# lipovsky-control.net
KiCad netlist of a schematic drawn in EAGLE
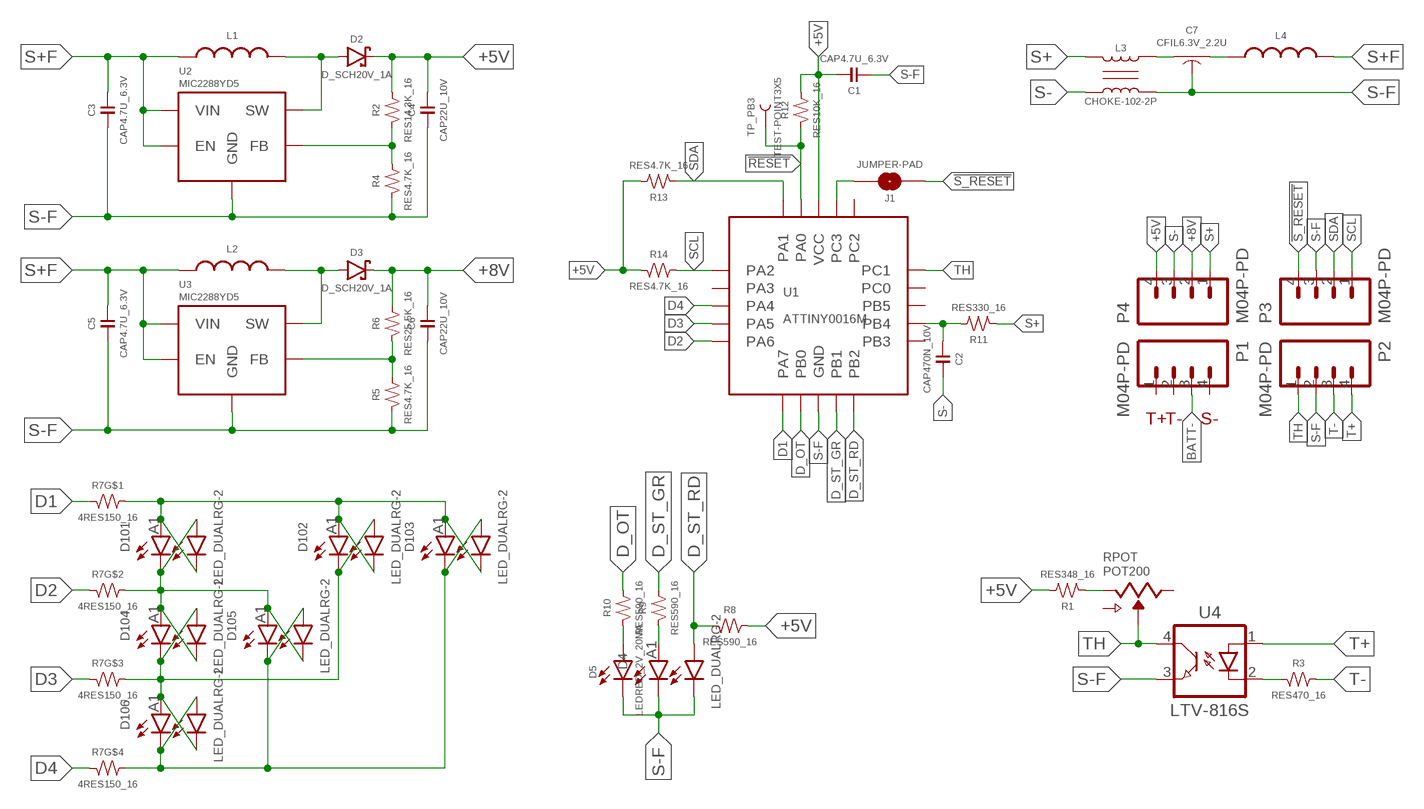
[diagram p0: schematic, sheet 1]

(export (version "E")
  (design (tool "Eeschema 10.0.6"))
  (components
    (comp (ref "C1")
      (value "CAP4.7U_6.3V")
      (footprint "eagle-import:0603")
      (fields
        (field (name "DIGIKEY_PART_#") "1276-2087-1-ND")
        (field (name "MANUFACTURER") "Samsung Electro-Mechanics America, Inc.")
        (field (name "MFG_PART_#") "CL10B475KQ8NQNC")
      )
      (libsource (lib "eagle-import") (part "CAP4.7U_6.3V"))
    )
    (comp (ref "C2")
      (value "CAP470N_10V")
      (footprint "eagle-import:0402")
      (fields
        (field (name "DIGIKEY_PART_#") "445-8009-1-ND")
        (field (name "MANUFACTURER") "TDK Corporation")
        (field (name "MFG_PART_#") "C1005X7S1A474K050BC")
      )
      (libsource (lib "eagle-import") (part "CAP470N_10V"))
    )
    (comp (ref "C3")
      (value "CAP4.7U_6.3V")
      (footprint "eagle-import:0603")
      (fields
        (field (name "DIGIKEY_PART_#") "1276-2087-1-ND")
        (field (name "MANUFACTURER") "Samsung Electro-Mechanics America, Inc.")
        (field (name "MFG_PART_#") "CL10B475KQ8NQNC")
      )
      (libsource (lib "eagle-import") (part "CAP4.7U_6.3V"))
    )
    (comp (ref "C4")
      (value "CAP22U_10V")
      (footprint "eagle-import:0603")
      (fields
        (field (name "DIGIKEY_PART_#") "1276-6504-1-ND")
        (field (name "MANUFACTURER") "Samsung Electro-Mechanics America, Inc.")
        (field (name "MFG_PART_#") "CL10A226MPCNUBE")
      )
      (libsource (lib "eagle-import") (part "CAP22U_10V"))
    )
    (comp (ref "C5")
      (value "CAP4.7U_6.3V")
      (footprint "eagle-import:0603")
      (fields
        (field (name "DIGIKEY_PART_#") "1276-2087-1-ND")
        (field (name "MANUFACTURER") "Samsung Electro-Mechanics America, Inc.")
        (field (name "MFG_PART_#") "CL10B475KQ8NQNC")
      )
      (libsource (lib "eagle-import") (part "CAP4.7U_6.3V"))
    )
    (comp (ref "C6")
      (value "CAP22U_10V")
      (footprint "eagle-import:0603")
      (fields
        (field (name "DIGIKEY_PART_#") "1276-6504-1-ND")
        (field (name "MANUFACTURER") "Samsung Electro-Mechanics America, Inc.")
        (field (name "MFG_PART_#") "CL10A226MPCNUBE")
      )
      (libsource (lib "eagle-import") (part "CAP22U_10V"))
    )
    (comp (ref "C7")
      (value "CFIL6.3V_2.2U")
      (footprint "eagle-import:CFIL-0603")
      (fields
        (field (name "MANUFACTURER") "Murata Electronics")
        (field (name "MFG_PART_#") "NFM18PC225B0J3D")
        (field (name "MOUSER_PART_#") "81-NFM18PC225B0J3D")
      )
      (libsource (lib "eagle-import") (part "CFIL6.3V_2.2U"))
    )
    (comp (ref "D2")
      (value "D_SCH20V_1A")
      (footprint "eagle-import:SOD523+")
      (fields
        (field (name "MANUFACTURER") "Nexperia")
        (field (name "MFG_PART_#") "PMEG2010AEB,115")
        (field (name "MOUSER_PART_#") "771-PMEG2010AEBT/R")
      )
      (libsource (lib "eagle-import") (part "D_SCH20V_1A"))
    )
    (comp (ref "D3")
      (value "D_SCH20V_1A")
      (footprint "eagle-import:SOD523+")
      (fields
        (field (name "MANUFACTURER") "Nexperia")
        (field (name "MFG_PART_#") "PMEG2010AEB,115")
        (field (name "MOUSER_PART_#") "771-PMEG2010AEBT/R")
      )
      (libsource (lib "eagle-import") (part "D_SCH20V_1A"))
    )
    (comp (ref "D4")
      (value "LED_DUALRG-2")
      (footprint "eagle-import:1206+DUAL")
      (fields
        (field (name "DIGIKEY_PART_#") "160-2026-1-ND")
        (field (name "MANUFACTURER") "Lite-On Inc.")
        (field (name "MFG_PART_#") "LTST-C235KGKRKT")
      )
      (libsource (lib "eagle-import") (part "LED_DUALRG-2"))
    )
    (comp (ref "D5")
      (value "LEDRED_2V_20MA")
      (footprint "eagle-import:1206+")
      (fields
        (field (name "DIGIKEY_PART_#") "160-1457-1-ND")
        (field (name "MANUFACTURER") "Lite-On Inc.")
        (field (name "MFG_PART_#") "LTST-C230KRKT")
      )
      (libsource (lib "eagle-import") (part "LEDRED_2V_20MA"))
    )
    (comp (ref "D101")
      (value "LED_DUALRG-2")
      (footprint "eagle-import:1206+DUAL")
      (fields
        (field (name "DIGIKEY_PART_#") "160-2026-1-ND")
        (field (name "MANUFACTURER") "Lite-On Inc.")
        (field (name "MFG_PART_#") "LTST-C235KGKRKT")
      )
      (libsource (lib "eagle-import") (part "LED_DUALRG-2"))
    )
    (comp (ref "D102")
      (value "LED_DUALRG-2")
      (footprint "eagle-import:1206+DUAL")
      (fields
        (field (name "DIGIKEY_PART_#") "160-2026-1-ND")
        (field (name "MANUFACTURER") "Lite-On Inc.")
        (field (name "MFG_PART_#") "LTST-C235KGKRKT")
      )
      (libsource (lib "eagle-import") (part "LED_DUALRG-2"))
    )
    (comp (ref "D103")
      (value "LED_DUALRG-2")
      (footprint "eagle-import:1206+DUAL")
      (fields
        (field (name "DIGIKEY_PART_#") "160-2026-1-ND")
        (field (name "MANUFACTURER") "Lite-On Inc.")
        (field (name "MFG_PART_#") "LTST-C235KGKRKT")
      )
      (libsource (lib "eagle-import") (part "LED_DUALRG-2"))
    )
    (comp (ref "D104")
      (value "LED_DUALRG-2")
      (footprint "eagle-import:1206+DUAL")
      (fields
        (field (name "DIGIKEY_PART_#") "160-2026-1-ND")
        (field (name "MANUFACTURER") "Lite-On Inc.")
        (field (name "MFG_PART_#") "LTST-C235KGKRKT")
      )
      (libsource (lib "eagle-import") (part "LED_DUALRG-2"))
    )
    (comp (ref "D105")
      (value "LED_DUALRG-2")
      (footprint "eagle-import:1206+DUAL")
      (fields
        (field (name "DIGIKEY_PART_#") "160-2026-1-ND")
        (field (name "MANUFACTURER") "Lite-On Inc.")
        (field (name "MFG_PART_#") "LTST-C235KGKRKT")
      )
      (libsource (lib "eagle-import") (part "LED_DUALRG-2"))
    )
    (comp (ref "D106")
      (value "LED_DUALRG-2")
      (footprint "eagle-import:1206+DUAL")
      (fields
        (field (name "DIGIKEY_PART_#") "160-2026-1-ND")
        (field (name "MANUFACTURER") "Lite-On Inc.")
        (field (name "MFG_PART_#") "LTST-C235KGKRKT")
      )
      (libsource (lib "eagle-import") (part "LED_DUALRG-2"))
    )
    (comp (ref "J1")
      (value "JUMPER-PAD")
      (footprint "eagle-import:JUMPER-PAD-ROUND")
      (libsource (lib "eagle-import") (part "JUMPER-PAD"))
    )
    (comp (ref "L1")
      (value "I4.7U_0.12A")
      (footprint "eagle-import:0603")
      (fields
        (field (name "DIGIKEY_PART_#") "445-6390-1-ND")
        (field (name "MANUFACTURER") "TDK Corporation")
        (field (name "MFG_PART_#") "MLZ1608M4R7WT000")
      )
      (libsource (lib "eagle-import") (part "I4.7U_0.12A"))
    )
    (comp (ref "L2")
      (value "I10U_0.09A")
      (footprint "eagle-import:0603")
      (fields
        (field (name "DIGIKEY_PART_#") "445-6389-1-ND")
        (field (name "MANUFACTURER") "TDK Corporation")
        (field (name "MFG_PART_#") "MLZ1608M100WT000")
      )
      (libsource (lib "eagle-import") (part "I10U_0.09A"))
    )
    (comp (ref "L3")
      (value "CHOKE-102-2P")
      (footprint "eagle-import:APC3225")
      (fields
        (field (name "DIGIKEY_PART_#") "445-174210-1-ND")
        (field (name "MANUFACTURER") "TDK Corporation")
        (field (name "MFG_PART_#") "ACP3225-102-2P-TL000")
      )
      (libsource (lib "eagle-import") (part "CHOKE-102-2P"))
    )
    (comp (ref "L4")
      (value "I3.3UH_1A")
      (footprint "eagle-import:0603")
      (fields
        (field (name "DIGIKEY_PART_#") "490-15635-1-ND")
        (field (name "MANUFACTURER") "Murata Electronics North America")
        (field (name "MFG_PART_#") "LQM18PN3R3MGHD")
      )
      (libsource (lib "eagle-import") (part "I3.3UH_1A"))
    )
    (comp (ref "P1")
      (value "M04P-PD")
      (footprint "eagle-import:1X04_929P")
      (fields
        (field (name "DIGIKEY_PART_#") "890-70-004-10-001101-ND")
        (field (name "MANUFACTURER") "Preci-dip")
        (field (name "MFG_PART_#") "890-70-004-10-001101")
      )
      (libsource (lib "eagle-import") (part "M04P-PD"))
    )
    (comp (ref "P2")
      (value "M04P-PD")
      (footprint "eagle-import:1X04_929P")
      (fields
        (field (name "DIGIKEY_PART_#") "890-70-004-10-001101-ND")
        (field (name "MANUFACTURER") "Preci-dip")
        (field (name "MFG_PART_#") "890-70-004-10-001101")
      )
      (libsource (lib "eagle-import") (part "M04P-PD"))
    )
    (comp (ref "P3")
      (value "M04P-PD")
      (footprint "eagle-import:1X04_929P")
      (fields
        (field (name "DIGIKEY_PART_#") "890-70-004-10-001101-ND")
        (field (name "MANUFACTURER") "Preci-dip")
        (field (name "MFG_PART_#") "890-70-004-10-001101")
      )
      (libsource (lib "eagle-import") (part "M04P-PD"))
    )
    (comp (ref "P4")
      (value "M04P-PD")
      (footprint "eagle-import:1X04_929P")
      (fields
        (field (name "DIGIKEY_PART_#") "890-70-004-10-001101-ND")
        (field (name "MANUFACTURER") "Preci-dip")
        (field (name "MFG_PART_#") "890-70-004-10-001101")
      )
      (libsource (lib "eagle-import") (part "M04P-PD"))
    )
    (comp (ref "R1")
      (value "RES348_16")
      (footprint "eagle-import:0402")
      (fields
        (field (name "DIGIKEY_PART_#") "541-348LCT-ND")
        (field (name "MANUFACTURER") "Vishay Dale")
        (field (name "MFG_PART_#") "CRCW0402348RFKED")
      )
      (libsource (lib "eagle-import") (part "RES348_16"))
    )
    (comp (ref "R2")
      (value "RES14.3K_16")
      (footprint "eagle-import:0402")
      (fields
        (field (name "DIGIKEY_PART_#") "541-14.3KLCT-ND")
        (field (name "MANUFACTURER") "Vishay Dale")
        (field (name "MFG_PART_#") "CRCW040214K3FKED")
      )
      (libsource (lib "eagle-import") (part "RES14.3K_16"))
    )
    (comp (ref "R3")
      (value "RES470_16")
      (footprint "eagle-import:0402")
      (fields
        (field (name "DIGIKEY_PART_#") "541-470LCT-ND")
        (field (name "MANUFACTURER") "Vishay Dale")
        (field (name "MFG_PART_#") "CRCW0402470RFKED")
      )
      (libsource (lib "eagle-import") (part "RES470_16"))
    )
    (comp (ref "R4")
      (value "RES4.7K_16")
      (footprint "eagle-import:0402")
      (fields
        (field (name "DIGIKEY_PART_#") "541-4.70KLCT-ND")
        (field (name "MANUFACTURER") "Vishay Dale")
        (field (name "MFG_PART_#") "CRCW04024K70FKED")
      )
      (libsource (lib "eagle-import") (part "RES4.7K_16"))
    )
    (comp (ref "R5")
      (value "RES4.7K_16")
      (footprint "eagle-import:0402")
      (fields
        (field (name "DIGIKEY_PART_#") "541-4.70KLCT-ND")
        (field (name "MANUFACTURER") "Vishay Dale")
        (field (name "MFG_PART_#") "CRCW04024K70FKED")
      )
      (libsource (lib "eagle-import") (part "RES4.7K_16"))
    )
    (comp (ref "R6")
      (value "RES25.5K_16")
      (footprint "eagle-import:0402")
      (fields
        (field (name "DIGIKEY_PART_#") "541-25.5KLCT-ND")
        (field (name "MANUFACTURER") "Vishay Dale")
        (field (name "MFG_PART_#") "CRCW040225K5FKED")
      )
      (libsource (lib "eagle-import") (part "RES25.5K_16"))
    )
    (comp (ref "R7")
      (value "4RES150_16")
      (footprint "eagle-import:1206-QUAD-LS")
      (fields
        (field (name "DIGIKEY_PART_#") "Y4151CT-ND")
        (field (name "MANUFACTURER") "Panasonic Electronic Components")
        (field (name "MFG_PART_#") "EXB-V8V151JV")
      )
      (libsource (lib "eagle-import") (part "4RES150_16"))
    )
    (comp (ref "R8")
      (value "RES590_16")
      (footprint "eagle-import:0402")
      (fields
        (field (name "DIGIKEY_PART_#") "541-590LCT-ND")
        (field (name "MANUFACTURER") "Vishay Dale")
        (field (name "MFG_PART_#") "CRCW0402590RFKED")
      )
      (libsource (lib "eagle-import") (part "RES590_16"))
    )
    (comp (ref "R9")
      (value "RES590_16")
      (footprint "eagle-import:0402")
      (fields
        (field (name "DIGIKEY_PART_#") "541-590LCT-ND")
        (field (name "MANUFACTURER") "Vishay Dale")
        (field (name "MFG_PART_#") "CRCW0402590RFKED")
      )
      (libsource (lib "eagle-import") (part "RES590_16"))
    )
    (comp (ref "R10")
      (value "RES590_16")
      (footprint "eagle-import:0402")
      (fields
        (field (name "DIGIKEY_PART_#") "541-590LCT-ND")
        (field (name "MANUFACTURER") "Vishay Dale")
        (field (name "MFG_PART_#") "CRCW0402590RFKED")
      )
      (libsource (lib "eagle-import") (part "RES590_16"))
    )
    (comp (ref "R11")
      (value "RES330_16")
      (footprint "eagle-import:0402")
      (fields
        (field (name "DIGIKEY_PART_#") "541-330LCT-ND")
        (field (name "MANUFACTURER") "Vishay Dale")
        (field (name "MFG_PART_#") "CRCW0402330RFKED")
      )
      (libsource (lib "eagle-import") (part "RES330_16"))
    )
    (comp (ref "R12")
      (value "RES10K_16")
      (footprint "eagle-import:0402")
      (fields
        (field (name "DIGIKEY_PART_#") "541-10.0KLCT-ND")
        (field (name "MANUFACTURER") "Vishay Dale")
        (field (name "MFG_PART_#") "CRCW040210K0FKED")
      )
      (libsource (lib "eagle-import") (part "RES10K_16"))
    )
    (comp (ref "R13")
      (value "RES4.7K_16")
      (footprint "eagle-import:0402")
      (fields
        (field (name "DIGIKEY_PART_#") "541-4.70KLCT-ND")
        (field (name "MANUFACTURER") "Vishay Dale")
        (field (name "MFG_PART_#") "CRCW04024K70FKED")
      )
      (libsource (lib "eagle-import") (part "RES4.7K_16"))
    )
    (comp (ref "R14")
      (value "RES4.7K_16")
      (footprint "eagle-import:0402")
      (fields
        (field (name "DIGIKEY_PART_#") "541-4.70KLCT-ND")
        (field (name "MANUFACTURER") "Vishay Dale")
        (field (name "MFG_PART_#") "CRCW04024K70FKED")
      )
      (libsource (lib "eagle-import") (part "RES4.7K_16"))
    )
    (comp (ref "RPOT")
      (value "POT200")
      (footprint "eagle-import:TC33")
      (fields
        (field (name "DIGIKEY_PART_#") "TC33X-2-201ECT-ND")
        (field (name "MANUFACTURER") "Bourns Inc.")
        (field (name "MFG_PART_#") "TC33X-2-201E")
      )
      (libsource (lib "eagle-import") (part "POT200"))
    )
    (comp (ref "TP_PB3")
      (value "TEST-POINT3X5")
      (footprint "eagle-import:PAD.03X.05")
      (libsource (lib "eagle-import") (part "TEST-POINT3X5"))
    )
    (comp (ref "U1")
      (value "ATTINY0016M")
      (footprint "eagle-import:20-VQFN-2")
      (fields
        (field (name "DIGIKEY_PART_#") "ATTINY1616-MFRCT-ND")
        (field (name "MANUFACTURER") "Microchip Technology")
        (field (name "MFG_PART_#") "ATTINY1616-MFR")
      )
      (libsource (lib "eagle-import") (part "ATTINY0016M"))
    )
    (comp (ref "U2")
      (value "MIC2288YD5")
      (footprint "eagle-import:SOT-23-5")
      (fields
        (field (name "DIGIKEY_PART_#") "576-1729-1-ND")
        (field (name "MANUFACTURER") "Microchip Technology")
        (field (name "MFG_PART_#") "MIC2288YD5-TR")
      )
      (libsource (lib "eagle-import") (part "MIC2288YD5"))
    )
    (comp (ref "U3")
      (value "MIC2288YD5")
      (footprint "eagle-import:SOT-23-5")
      (fields
        (field (name "DIGIKEY_PART_#") "576-1729-1-ND")
        (field (name "MANUFACTURER") "Microchip Technology")
        (field (name "MFG_PART_#") "MIC2288YD5-TR")
      )
      (libsource (lib "eagle-import") (part "MIC2288YD5"))
    )
    (comp (ref "U4")
      (value "LTV-816S")
      (footprint "eagle-import:4-OPTO-1")
      (fields (field (name "DIGIKEY_PART_#") "160-1361-5-ND") (field (name "MANUFACTURER") "Lite-On Inc."))
      (libsource (lib "eagle-import") (part "LTV-816S"))
    )
  )
  (nets
    (net (code "1") (name "+5V") (class "Default")
      (node (ref "C1") (pin "2") (pinfunction "2_2") (pintype "passive"))
      (node (ref "C4") (pin "2") (pinfunction "2_2") (pintype "passive"))
      (node (ref "D2") (pin "C") (pinfunction "C_C") (pintype "passive"))
      (node (ref "P4") (pin "4") (pinfunction "4_4") (pintype "passive"))
      (node (ref "R1") (pin "2") (pinfunction "2_2") (pintype "passive"))
      (node (ref "R12") (pin "2") (pinfunction "2_2") (pintype "passive"))
      (node (ref "R13") (pin "2") (pinfunction "2_2") (pintype "passive"))
      (node (ref "R14") (pin "1") (pinfunction "1_1") (pintype "passive"))
      (node (ref "R2") (pin "2") (pinfunction "2_2") (pintype "passive"))
      (node (ref "R8") (pin "2") (pinfunction "2_2") (pintype "passive"))
      (node (ref "U1") (pin "4") (pinfunction "VCC_4") (pintype "passive"))
    )
    (net (code "2") (name "+8V") (class "Default")
      (node (ref "C6") (pin "2") (pinfunction "2_2") (pintype "passive"))
      (node (ref "D3") (pin "C") (pinfunction "C_C") (pintype "passive"))
      (node (ref "P4") (pin "2") (pinfunction "2_2") (pintype "passive"))
      (node (ref "R6") (pin "2") (pinfunction "2_2") (pintype "passive"))
    )
    (net (code "3") (name "/~{RESET}") (class "Default")
      (node (ref "R12") (pin "1") (pinfunction "1_1") (pintype "passive"))
      (node (ref "TP_PB3") (pin "P$1") (pinfunction "1_P$1") (pintype "bidirectional"))
      (node (ref "U1") (pin "19") (pinfunction "PA0_19") (pintype "passive"))
    )
    (net (code "4") (name "/~{S_RESET}") (class "Default")
      (node (ref "J1") (pin "1") (pinfunction "1_1") (pintype "passive"))
      (node (ref "P3") (pin "4") (pinfunction "4_4") (pintype "passive"))
    )
    (net (code "5") (name "BATT-") (class "Default")
      (node (ref "P1") (pin "3") (pinfunction "3_3") (pintype "passive"))
    )
    (net (code "6") (name "D1") (class "Default")
      (node (ref "R7") (pin "1") (pinfunction "1_1") (pintype "passive"))
      (node (ref "U1") (pin "8") (pinfunction "PA7_8") (pintype "passive"))
    )
    (net (code "7") (name "D2") (class "Default")
      (node (ref "R7") (pin "2") (pinfunction "1_2") (pintype "passive"))
      (node (ref "U1") (pin "7") (pinfunction "PA6_7") (pintype "passive"))
    )
    (net (code "8") (name "D3") (class "Default")
      (node (ref "R7") (pin "3") (pinfunction "1_3") (pintype "passive"))
      (node (ref "U1") (pin "6") (pinfunction "PA5_6") (pintype "passive"))
    )
    (net (code "9") (name "D4") (class "Default")
      (node (ref "R7") (pin "4") (pinfunction "1_4") (pintype "passive"))
      (node (ref "U1") (pin "5") (pinfunction "PA4_5") (pintype "passive"))
    )
    (net (code "10") (name "D_OT") (class "Default")
      (node (ref "R10") (pin "2") (pinfunction "2_2") (pintype "passive"))
      (node (ref "U1") (pin "14") (pinfunction "PB0_14") (pintype "passive"))
    )
    (net (code "11") (name "D_ST_GR") (class "Default")
      (node (ref "R9") (pin "2") (pinfunction "2_2") (pintype "passive"))
      (node (ref "U1") (pin "13") (pinfunction "PB1_13") (pintype "passive"))
    )
    (net (code "12") (name "D_ST_RD") (class "Default")
      (node (ref "D4") (pin "A2") (pinfunction "A2_A2") (pintype "passive"))
      (node (ref "R8") (pin "1") (pinfunction "1_1") (pintype "passive"))
      (node (ref "U1") (pin "12") (pinfunction "PB2_12") (pintype "passive"))
    )
    (net (code "13") (name "Net-(C7-Pad2)") (class "Default")
      (node (ref "C7") (pin "2") (pinfunction "2_2") (pintype "passive"))
      (node (ref "L4") (pin "1") (pinfunction "1_1") (pintype "passive"))
    )
    (net (code "14") (name "Net-(D4-PadA1)") (class "Default")
      (node (ref "D4") (pin "A1") (pinfunction "A1_A1") (pintype "passive"))
      (node (ref "R9") (pin "1") (pinfunction "1_1") (pintype "passive"))
    )
    (net (code "15") (name "Net-(D5-PadA)") (class "Default")
      (node (ref "D5") (pin "A") (pinfunction "A_A") (pintype "passive"))
      (node (ref "R10") (pin "1") (pinfunction "1_1") (pintype "passive"))
    )
    (net (code "16") (name "Net-(L3-4)") (class "Default")
      (node (ref "C7") (pin "1") (pinfunction "1_1") (pintype "passive"))
      (node (ref "L3") (pin "P$4") (pinfunction "4_P$4") (pintype "passive"))
    )
    (net (code "17") (name "Net-(R1-Pad1)") (class "Default")
      (node (ref "R1") (pin "1") (pinfunction "1_1") (pintype "passive"))
      (node (ref "RPOT") (pin "CCW") (pinfunction "CCW_CCW") (pintype "passive"))
    )
    (net (code "18") (name "Net-(R7A-2)") (class "Default")
      (node (ref "D101") (pin "A1") (pinfunction "A1_A1") (pintype "passive"))
      (node (ref "D101") (pin "C2") (pinfunction "C2_C2") (pintype "passive"))
      (node (ref "D102") (pin "A1") (pinfunction "A1_A1") (pintype "passive"))
      (node (ref "D102") (pin "C2") (pinfunction "C2_C2") (pintype "passive"))
      (node (ref "D103") (pin "A1") (pinfunction "A1_A1") (pintype "passive"))
      (node (ref "D103") (pin "C2") (pinfunction "C2_C2") (pintype "passive"))
      (node (ref "R7") (pin "8") (pinfunction "2_8") (pintype "passive"))
    )
    (net (code "19") (name "Net-(R7B-2)") (class "Default")
      (node (ref "D101") (pin "A2") (pinfunction "A2_A2") (pintype "passive"))
      (node (ref "D101") (pin "C1") (pinfunction "C1_C1") (pintype "passive"))
      (node (ref "D104") (pin "A1") (pinfunction "A1_A1") (pintype "passive"))
      (node (ref "D104") (pin "C2") (pinfunction "C2_C2") (pintype "passive"))
      (node (ref "D105") (pin "A1") (pinfunction "A1_A1") (pintype "passive"))
      (node (ref "D105") (pin "C2") (pinfunction "C2_C2") (pintype "passive"))
      (node (ref "R7") (pin "7") (pinfunction "2_7") (pintype "passive"))
    )
    (net (code "20") (name "Net-(R7C-2)") (class "Default")
      (node (ref "D102") (pin "A2") (pinfunction "A2_A2") (pintype "passive"))
      (node (ref "D102") (pin "C1") (pinfunction "C1_C1") (pintype "passive"))
      (node (ref "D104") (pin "A2") (pinfunction "A2_A2") (pintype "passive"))
      (node (ref "D104") (pin "C1") (pinfunction "C1_C1") (pintype "passive"))
      (node (ref "D106") (pin "A1") (pinfunction "A1_A1") (pintype "passive"))
      (node (ref "D106") (pin "C2") (pinfunction "C2_C2") (pintype "passive"))
      (node (ref "R7") (pin "6") (pinfunction "2_6") (pintype "passive"))
    )
    (net (code "21") (name "Net-(R7D-2)") (class "Default")
      (node (ref "D103") (pin "A2") (pinfunction "A2_A2") (pintype "passive"))
      (node (ref "D103") (pin "C1") (pinfunction "C1_C1") (pintype "passive"))
      (node (ref "D105") (pin "A2") (pinfunction "A2_A2") (pintype "passive"))
      (node (ref "D105") (pin "C1") (pinfunction "C1_C1") (pintype "passive"))
      (node (ref "D106") (pin "A2") (pinfunction "A2_A2") (pintype "passive"))
      (node (ref "D106") (pin "C1") (pinfunction "C1_C1") (pintype "passive"))
      (node (ref "R7") (pin "5") (pinfunction "2_5") (pintype "passive"))
    )
    (net (code "22") (name "Net-(U1-PB4)") (class "Default")
      (node (ref "C2") (pin "1") (pinfunction "1_1") (pintype "passive"))
      (node (ref "R11") (pin "2") (pinfunction "2_2") (pintype "passive"))
      (node (ref "U1") (pin "10") (pinfunction "PB4_10") (pintype "passive"))
    )
    (net (code "23") (name "Net-(U1-PC3)") (class "Default")
      (node (ref "J1") (pin "2") (pinfunction "2_2") (pintype "passive"))
      (node (ref "U1") (pin "18") (pinfunction "PC3_18") (pintype "passive"))
    )
    (net (code "24") (name "Net-(U2-FB)") (class "Default")
      (node (ref "R2") (pin "1") (pinfunction "1_1") (pintype "passive"))
      (node (ref "R4") (pin "2") (pinfunction "2_2") (pintype "passive"))
      (node (ref "U2") (pin "3") (pinfunction "FB_3") (pintype "passive"))
    )
    (net (code "25") (name "Net-(U2-SW)") (class "Default")
      (node (ref "D2") (pin "A") (pinfunction "A_A") (pintype "passive"))
      (node (ref "L1") (pin "2") (pinfunction "2_2") (pintype "passive"))
      (node (ref "U2") (pin "1") (pinfunction "SW_1") (pintype "passive"))
    )
    (net (code "26") (name "Net-(U3-FB)") (class "Default")
      (node (ref "R5") (pin "2") (pinfunction "2_2") (pintype "passive"))
      (node (ref "R6") (pin "1") (pinfunction "1_1") (pintype "passive"))
      (node (ref "U3") (pin "3") (pinfunction "FB_3") (pintype "passive"))
    )
    (net (code "27") (name "Net-(U3-SW)") (class "Default")
      (node (ref "D3") (pin "A") (pinfunction "A_A") (pintype "passive"))
      (node (ref "L2") (pin "2") (pinfunction "2_2") (pintype "passive"))
      (node (ref "U3") (pin "1") (pinfunction "SW_1") (pintype "passive"))
    )
    (net (code "28") (name "Net-(U4-K)") (class "Default")
      (node (ref "R3") (pin "1") (pinfunction "1_1") (pintype "passive"))
      (node (ref "U4") (pin "2") (pinfunction "K_2") (pintype "passive"))
    )
    (net (code "29") (name "S+") (class "Default")
      (node (ref "L3") (pin "P$1") (pinfunction "1_P$1") (pintype "passive"))
      (node (ref "P4") (pin "1") (pinfunction "1_1") (pintype "passive"))
      (node (ref "R11") (pin "1") (pinfunction "1_1") (pintype "passive"))
    )
    (net (code "30") (name "S+F") (class "Default")
      (node (ref "C3") (pin "2") (pinfunction "2_2") (pintype "passive"))
      (node (ref "C5") (pin "2") (pinfunction "2_2") (pintype "passive"))
      (node (ref "L1") (pin "1") (pinfunction "1_1") (pintype "passive"))
      (node (ref "L2") (pin "1") (pinfunction "1_1") (pintype "passive"))
      (node (ref "L4") (pin "2") (pinfunction "2_2") (pintype "passive"))
      (node (ref "U2") (pin "4") (pinfunction "EN_4") (pintype "passive"))
      (node (ref "U2") (pin "5") (pinfunction "VIN_5") (pintype "passive"))
      (node (ref "U3") (pin "4") (pinfunction "EN_4") (pintype "passive"))
      (node (ref "U3") (pin "5") (pinfunction "VIN_5") (pintype "passive"))
    )
    (net (code "31") (name "S-") (class "Default")
      (node (ref "C2") (pin "2") (pinfunction "2_2") (pintype "passive"))
      (node (ref "L3") (pin "P$2") (pinfunction "2_P$2") (pintype "passive"))
      (node (ref "P4") (pin "3") (pinfunction "3_3") (pintype "passive"))
    )
    (net (code "32") (name "S-F") (class "Default")
      (node (ref "C1") (pin "1") (pinfunction "1_1") (pintype "passive"))
      (node (ref "C3") (pin "1") (pinfunction "1_1") (pintype "passive"))
      (node (ref "C4") (pin "1") (pinfunction "1_1") (pintype "passive"))
      (node (ref "C5") (pin "1") (pinfunction "1_1") (pintype "passive"))
      (node (ref "C6") (pin "1") (pinfunction "1_1") (pintype "passive"))
      (node (ref "C7") (pin "GND") (pinfunction "GND_GND") (pintype "passive"))
      (node (ref "D4") (pin "C1") (pinfunction "C1_C1") (pintype "passive"))
      (node (ref "D4") (pin "C2") (pinfunction "C2_C2") (pintype "passive"))
      (node (ref "D5") (pin "C") (pinfunction "C_C") (pintype "passive"))
      (node (ref "L3") (pin "P$3") (pinfunction "3_P$3") (pintype "passive"))
      (node (ref "P2") (pin "2") (pinfunction "2_2") (pintype "passive"))
      (node (ref "P3") (pin "3") (pinfunction "3_3") (pintype "passive"))
      (node (ref "R4") (pin "1") (pinfunction "1_1") (pintype "passive"))
      (node (ref "R5") (pin "1") (pinfunction "1_1") (pintype "passive"))
      (node (ref "U1") (pin "3") (pinfunction "GND_3") (pintype "passive"))
      (node (ref "U1") (pin "PAD") (pinfunction "GND_PAD") (pintype "passive"))
      (node (ref "U2") (pin "2") (pinfunction "GND_2") (pintype "passive"))
      (node (ref "U3") (pin "2") (pinfunction "GND_2") (pintype "passive"))
      (node (ref "U4") (pin "3") (pinfunction "E_3") (pintype "passive"))
    )
    (net (code "33") (name "SCL") (class "Default")
      (node (ref "P3") (pin "1") (pinfunction "1_1") (pintype "passive"))
      (node (ref "R14") (pin "2") (pinfunction "2_2") (pintype "passive"))
      (node (ref "U1") (pin "1") (pinfunction "PA2_1") (pintype "passive"))
    )
    (net (code "34") (name "SDA") (class "Default")
      (node (ref "P3") (pin "2") (pinfunction "2_2") (pintype "passive"))
      (node (ref "R13") (pin "1") (pinfunction "1_1") (pintype "passive"))
      (node (ref "U1") (pin "20") (pinfunction "PA1_20") (pintype "passive"))
    )
    (net (code "35") (name "T+") (class "Default")
      (node (ref "P2") (pin "4") (pinfunction "4_4") (pintype "passive"))
      (node (ref "U4") (pin "1") (pinfunction "A_1") (pintype "passive"))
    )
    (net (code "36") (name "T-") (class "Default")
      (node (ref "P2") (pin "3") (pinfunction "3_3") (pintype "passive"))
      (node (ref "R3") (pin "2") (pinfunction "2_2") (pintype "passive"))
    )
    (net (code "37") (name "TH") (class "Default")
      (node (ref "P2") (pin "1") (pinfunction "1_1") (pintype "passive"))
      (node (ref "RPOT") (pin "WIPER") (pinfunction "WIPER_WIPER") (pintype "passive"))
      (node (ref "U1") (pin "16") (pinfunction "PC1_16") (pintype "passive"))
      (node (ref "U4") (pin "4") (pinfunction "C_4") (pintype "passive"))
    )
    (net (code "38") (name "unconnected-(P1-Pad1)") (class "Default")
      (node (ref "P1") (pin "1") (pinfunction "1_1") (pintype "passive"))
    )
    (net (code "39") (name "unconnected-(P1-Pad2)") (class "Default")
      (node (ref "P1") (pin "2") (pinfunction "2_2") (pintype "passive"))
    )
    (net (code "40") (name "unconnected-(P1-Pad4)") (class "Default")
      (node (ref "P1") (pin "4") (pinfunction "4_4") (pintype "passive"))
    )
    (net (code "41") (name "unconnected-(RPOT-PadCW)") (class "Default")
      (node (ref "RPOT") (pin "CW") (pinfunction "CW_CW") (pintype "passive"))
    )
    (net (code "42") (name "unconnected-(U1-PA3-Pad2)") (class "Default")
      (node (ref "U1") (pin "2") (pinfunction "PA3_2") (pintype "passive"))
    )
    (net (code "43") (name "unconnected-(U1-PB3-Pad11)") (class "Default")
      (node (ref "U1") (pin "11") (pinfunction "PB3_11") (pintype "passive"))
    )
    (net (code "44") (name "unconnected-(U1-PB5-Pad9)") (class "Default")
      (node (ref "U1") (pin "9") (pinfunction "PB5_9") (pintype "passive"))
    )
    (net (code "45") (name "unconnected-(U1-PC0-Pad15)") (class "Default")
      (node (ref "U1") (pin "15") (pinfunction "PC0_15") (pintype "passive"))
    )
    (net (code "46") (name "unconnected-(U1-PC2-Pad17)") (class "Default")
      (node (ref "U1") (pin "17") (pinfunction "PC2_17") (pintype "passive"))
    )
  )
)
